# fractus_antenna.net
KiCad netlist of a schematic drawn in EAGLE
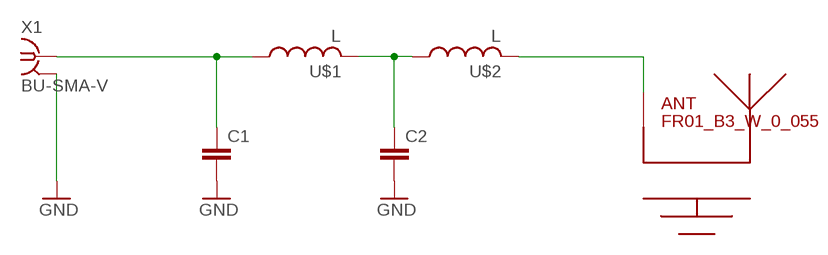
[diagram p0: schematic, sheet 1]

(export (version "E")
  (design (tool "Eeschema 10.0.6"))
  (components
    (comp (ref "ANT")
      (value "FR01_B3_W_0_055")
      (footprint "eagle-import:FR01_B3_W_0_055")
      (libsource (lib "eagle-import") (part "FR01_B3_W_0_055"))
    )
    (comp (ref "C1")
      (value "CC0603")
      (footprint "eagle-import:C0603")
      (libsource (lib "eagle-import") (part "CC0603"))
    )
    (comp (ref "C2")
      (value "CC0603")
      (footprint "eagle-import:C0603")
      (libsource (lib "eagle-import") (part "CC0603"))
    )
    (comp (ref "U$1")
      (value "L")
      (footprint "eagle-import:COILCRAFT_0805HP")
      (libsource (lib "eagle-import") (part "L"))
    )
    (comp (ref "U$2")
      (value "L")
      (footprint "eagle-import:COILCRAFT_0805HP")
      (libsource (lib "eagle-import") (part "L"))
    )
    (comp (ref "X1")
      (value "BU-SMA-V")
      (footprint "eagle-import:BU-SMA-V")
      (libsource (lib "eagle-import") (part "BU-SMA-V"))
    )
  )
  (nets
    (net (code "1") (name "GND") (class "Default")
      (node (ref "C1") (pin "2") (pinfunction "2_2") (pintype "passive"))
      (node (ref "C2") (pin "2") (pinfunction "2_2") (pintype "passive"))
      (node (ref "X1") (pin "2") (pinfunction "2_2") (pintype "passive"))
      (node (ref "X1") (pin "3") (pinfunction "2_3") (pintype "passive"))
      (node (ref "X1") (pin "4") (pinfunction "2_4") (pintype "passive"))
      (node (ref "X1") (pin "5") (pinfunction "2_5") (pintype "passive"))
    )
    (net (code "2") (name "Net-(ANT-PadFEED)") (class "Default")
      (node (ref "ANT") (pin "FEED") (pinfunction "FEED_FEED") (pintype "bidirectional"))
      (node (ref "U$2") (pin "2") (pinfunction "2_2") (pintype "passive"))
    )
    (net (code "3") (name "Net-(C1-Pad1)") (class "Default")
      (node (ref "C1") (pin "1") (pinfunction "1_1") (pintype "passive"))
      (node (ref "U$1") (pin "1") (pinfunction "1_1") (pintype "passive"))
      (node (ref "X1") (pin "1") (pinfunction "1_1") (pintype "passive"))
    )
    (net (code "4") (name "Net-(C2-Pad1)") (class "Default")
      (node (ref "C2") (pin "1") (pinfunction "1_1") (pintype "passive"))
      (node (ref "U$1") (pin "2") (pinfunction "2_2") (pintype "passive"))
      (node (ref "U$2") (pin "1") (pinfunction "1_1") (pintype "passive"))
    )
    (net (code "5") (name "unconnected-(ANT-PadMOUNT0)") (class "Default")
      (node (ref "ANT") (pin "MOUNT0") (pinfunction "MOUNT0_MOUNT0") (pintype "no_connect"))
    )
    (net (code "6") (name "unconnected-(ANT-PadMOUNT1)") (class "Default")
      (node (ref "ANT") (pin "MOUNT1") (pinfunction "MOUNT1_MOUNT1") (pintype "no_connect"))
    )
    (net (code "7") (name "unconnected-(ANT-PadMOUNT2)") (class "Default")
      (node (ref "ANT") (pin "MOUNT2") (pinfunction "MOUNT2_MOUNT2") (pintype "no_connect"))
    )
  )
)
